# avr_dip.net
KiCad netlist of a schematic drawn in EAGLE
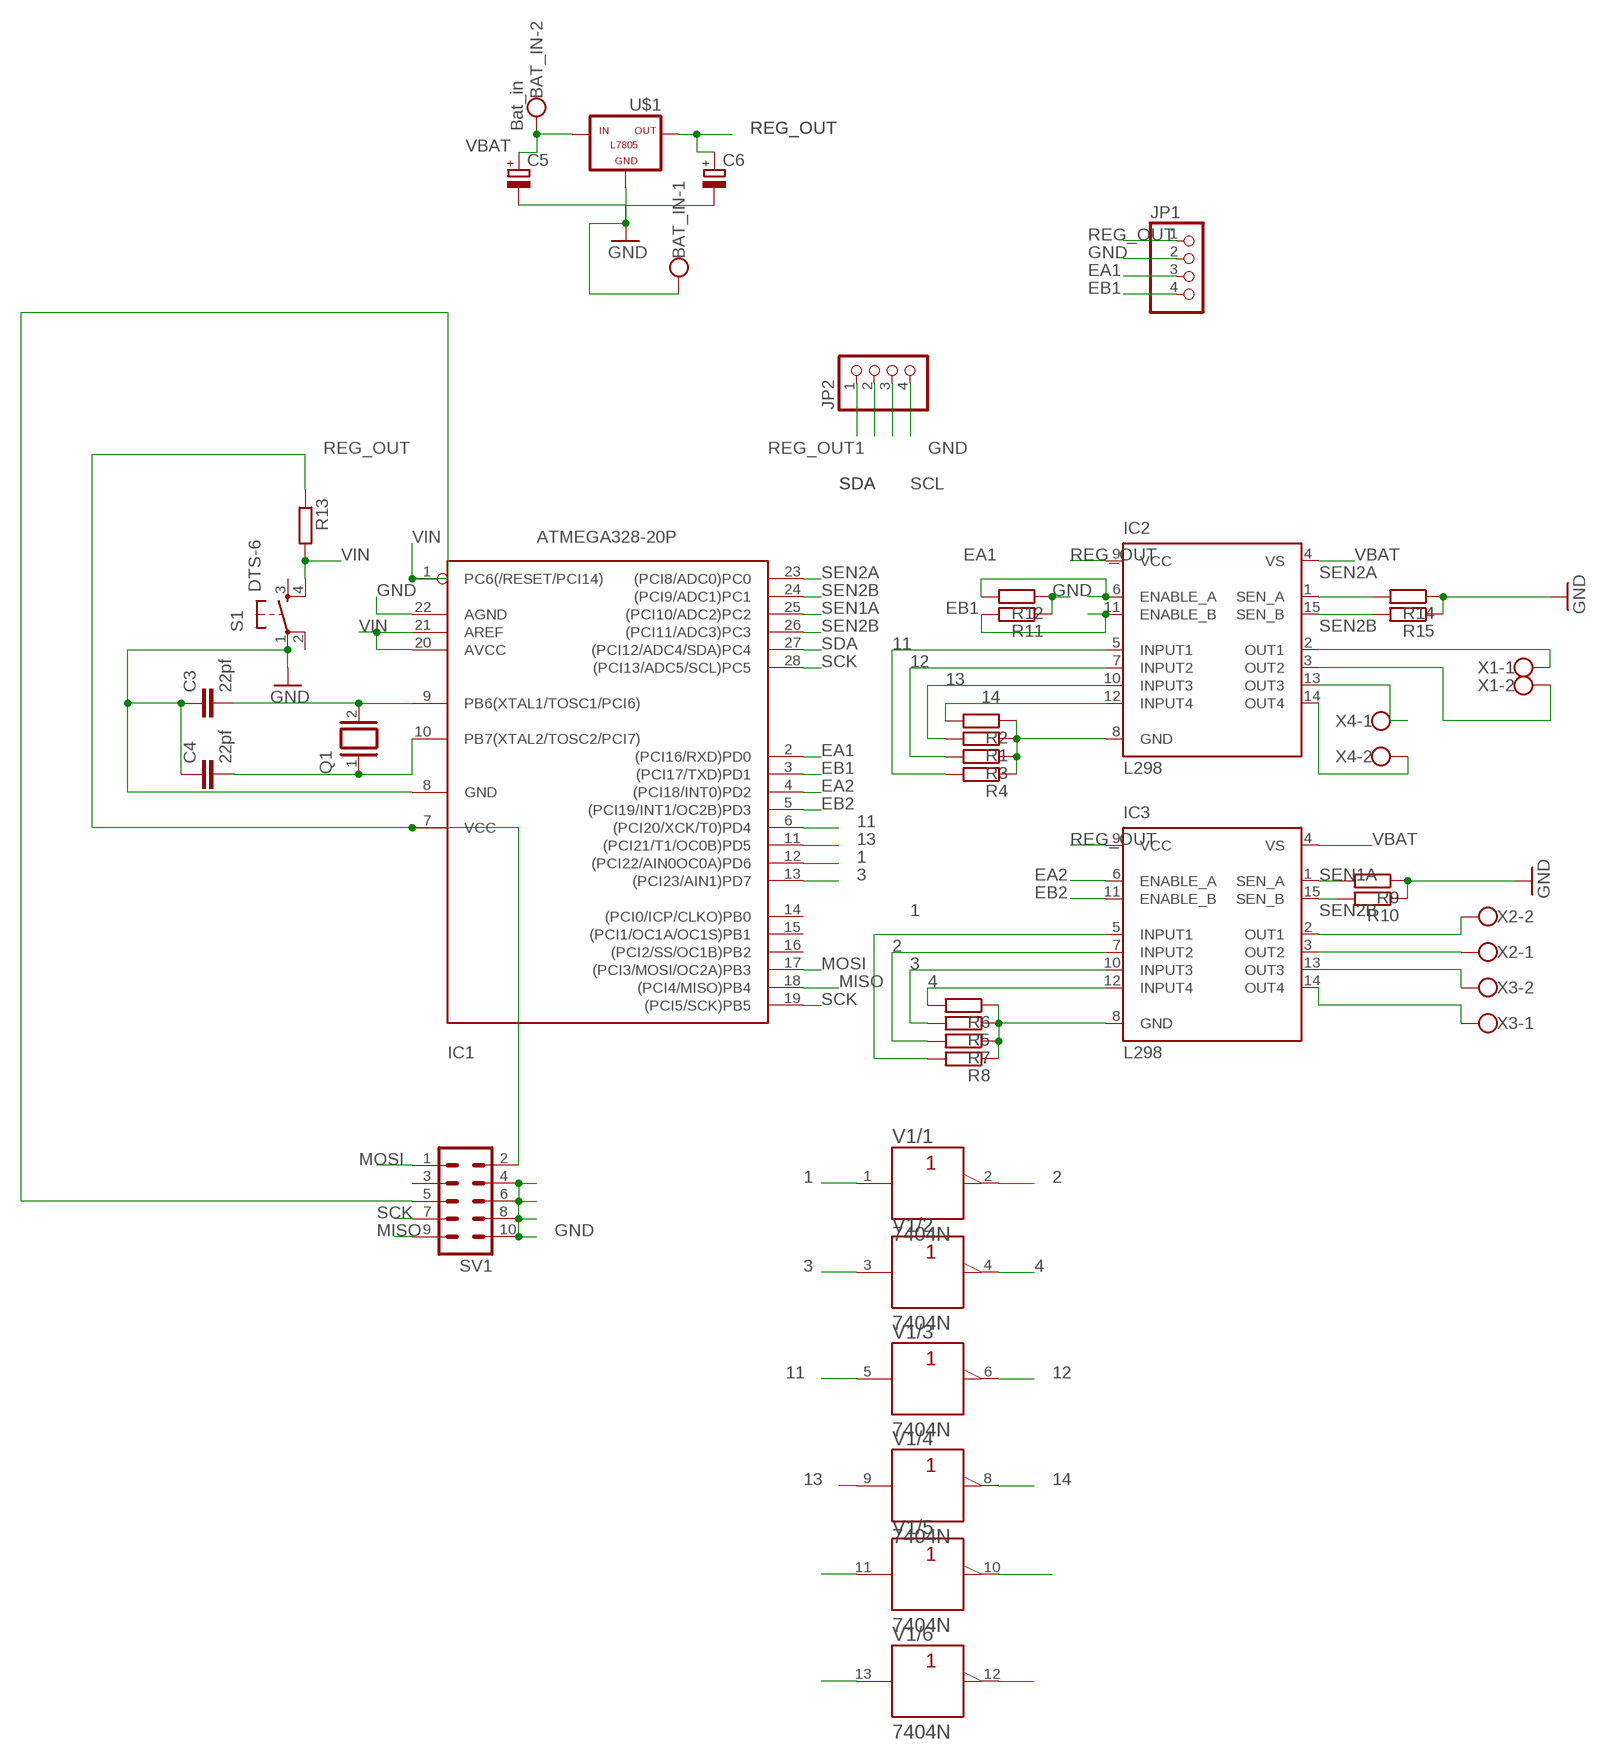
[diagram p0: schematic, sheet 1]

(export (version "E")
  (design (tool "Eeschema 10.0.6"))
  (components
    (comp (ref "BAT_IN")
      (value "Bat_in")
      (footprint "eagle-import:W237-102")
      (fields (field (name "MPN") "237-102"))
      (libsource (lib "eagle-import") (part "W237-102"))
    )
    (comp (ref "C3")
      (value "22pf")
      (footprint "eagle-import:C5B2.5")
      (libsource (lib "eagle-import") (part "C5/2.5"))
    )
    (comp (ref "C4")
      (value "22pf")
      (footprint "eagle-import:C5B2.5")
      (libsource (lib "eagle-import") (part "C5/2.5"))
    )
    (comp (ref "C5")
      (value "CPOL-EUE2-5")
      (footprint "eagle-import:E2-5")
      (libsource (lib "eagle-import") (part "CPOL-EUE2-5"))
    )
    (comp (ref "C6")
      (value "CPOL-EUE2-5")
      (footprint "eagle-import:E2-5")
      (libsource (lib "eagle-import") (part "CPOL-EUE2-5"))
    )
    (comp (ref "IC1")
      (value "ATMEGA328-20P")
      (footprint "eagle-import:DIL28-3")
      (libsource (lib "eagle-import") (part "ATMEGA328P-20"))
    )
    (comp (ref "IC2")
      (value "L298")
      (footprint "eagle-import:MULTIWATT-15")
      (fields (field (name "MPN") "L298N"))
      (libsource (lib "eagle-import") (part "L298"))
    )
    (comp (ref "IC3")
      (value "L298")
      (footprint "eagle-import:MULTIWATT-15")
      (fields (field (name "MPN") "L298N"))
      (libsource (lib "eagle-import") (part "L298"))
    )
    (comp (ref "JP1")
      (value "PINHD-1X4")
      (footprint "eagle-import:1X04")
      (libsource (lib "eagle-import") (part "PINHD-1X4"))
    )
    (comp (ref "JP2")
      (value "PINHD-1X4")
      (footprint "eagle-import:1X04")
      (libsource (lib "eagle-import") (part "PINHD-1X4"))
    )
    (comp (ref "Q1")
      (value "XTAL/S")
      (footprint "eagle-import:QS")
      (libsource (lib "eagle-import") (part "XTAL/S"))
    )
    (comp (ref "R1")
      (value "R-EU_0207/10")
      (footprint "eagle-import:0207_10")
      (libsource (lib "eagle-import") (part "R-EU_0207/10"))
    )
    (comp (ref "R2")
      (value "R-EU_0207/10")
      (footprint "eagle-import:0207_10")
      (libsource (lib "eagle-import") (part "R-EU_0207/10"))
    )
    (comp (ref "R3")
      (value "R-EU_0207/10")
      (footprint "eagle-import:0207_10")
      (libsource (lib "eagle-import") (part "R-EU_0207/10"))
    )
    (comp (ref "R4")
      (value "R-EU_0207/10")
      (footprint "eagle-import:0207_10")
      (libsource (lib "eagle-import") (part "R-EU_0207/10"))
    )
    (comp (ref "R5")
      (value "R-EU_0207/10")
      (footprint "eagle-import:0207_10")
      (libsource (lib "eagle-import") (part "R-EU_0207/10"))
    )
    (comp (ref "R6")
      (value "R-EU_0207/10")
      (footprint "eagle-import:0207_10")
      (libsource (lib "eagle-import") (part "R-EU_0207/10"))
    )
    (comp (ref "R7")
      (value "R-EU_0207/10")
      (footprint "eagle-import:0207_10")
      (libsource (lib "eagle-import") (part "R-EU_0207/10"))
    )
    (comp (ref "R8")
      (value "R-EU_0207/10")
      (footprint "eagle-import:0207_10")
      (libsource (lib "eagle-import") (part "R-EU_0207/10"))
    )
    (comp (ref "R9")
      (value "R-EU_0207/10")
      (footprint "eagle-import:0207_10")
      (libsource (lib "eagle-import") (part "R-EU_0207/10"))
    )
    (comp (ref "R10")
      (value "R-EU_0207/10")
      (footprint "eagle-import:0207_10")
      (libsource (lib "eagle-import") (part "R-EU_0207/10"))
    )
    (comp (ref "R11")
      (value "R-EU_0207/10")
      (footprint "eagle-import:0207_10")
      (libsource (lib "eagle-import") (part "R-EU_0207/10"))
    )
    (comp (ref "R12")
      (value "R-EU_0207/10")
      (footprint "eagle-import:0207_10")
      (libsource (lib "eagle-import") (part "R-EU_0207/10"))
    )
    (comp (ref "R13")
      (value "R-EU_0207/10")
      (footprint "eagle-import:0207_10")
      (libsource (lib "eagle-import") (part "R-EU_0207/10"))
    )
    (comp (ref "R14")
      (value "R-EU_0207/10")
      (footprint "eagle-import:0207_10")
      (libsource (lib "eagle-import") (part "R-EU_0207/10"))
    )
    (comp (ref "R15")
      (value "R-EU_0207/10")
      (footprint "eagle-import:0207_10")
      (libsource (lib "eagle-import") (part "R-EU_0207/10"))
    )
    (comp (ref "S1")
      (value "DTS-6")
      (footprint "eagle-import:DTS-6")
      (libsource (lib "eagle-import") (part "DTS-6"))
    )
    (comp (ref "SV1")
      (value "MA05-2")
      (footprint "eagle-import:MA05-2")
      (libsource (lib "eagle-import") (part "MA05-2"))
    )
    (comp (ref "U$1")
      (value "-L7805")
      (footprint "eagle-import:L7805")
      (libsource (lib "eagle-import") (part "-L7805"))
    )
    (comp (ref "V1")
      (value "7404N")
      (footprint "eagle-import:DIL14")
      (libsource (lib "eagle-import") (part "7404N"))
    )
    (comp (ref "X1")
      (value "W237-102")
      (footprint "eagle-import:W237-102")
      (fields (field (name "MPN") "237-102"))
      (libsource (lib "eagle-import") (part "W237-102"))
    )
    (comp (ref "X2")
      (value "W237-102")
      (footprint "eagle-import:W237-102")
      (fields (field (name "MPN") "237-102"))
      (libsource (lib "eagle-import") (part "W237-102"))
    )
    (comp (ref "X3")
      (value "W237-102")
      (footprint "eagle-import:W237-102")
      (fields (field (name "MPN") "237-102"))
      (libsource (lib "eagle-import") (part "W237-102"))
    )
    (comp (ref "X4")
      (value "W237-102")
      (footprint "eagle-import:W237-102")
      (fields (field (name "MPN") "237-102"))
      (libsource (lib "eagle-import") (part "W237-102"))
    )
  )
  (nets
    (net (code "1") (name "/1") (class "Default")
      (node (ref "IC1") (pin "12") (pinfunction "(PCI22/AIN0OC0A)PD6_12") (pintype "bidirectional"))
      (node (ref "IC3") (pin "5") (pinfunction "INPUT1_5") (pintype "input"))
      (node (ref "R8") (pin "2") (pinfunction "2_2") (pintype "passive"))
      (node (ref "V1") (pin "1") (pinfunction "A_1") (pintype "input"))
    )
    (net (code "2") (name "/2") (class "Default")
      (node (ref "IC3") (pin "7") (pinfunction "INPUT2_7") (pintype "input"))
      (node (ref "R7") (pin "2") (pinfunction "2_2") (pintype "passive"))
      (node (ref "V1") (pin "2") (pinfunction "Y_2") (pintype "output"))
    )
    (net (code "3") (name "/3") (class "Default")
      (node (ref "IC1") (pin "13") (pinfunction "(PCI23/AIN1)PD7_13") (pintype "bidirectional"))
      (node (ref "IC3") (pin "10") (pinfunction "INPUT3_10") (pintype "input"))
      (node (ref "R5") (pin "2") (pinfunction "2_2") (pintype "passive"))
      (node (ref "V1") (pin "3") (pinfunction "A_3") (pintype "input"))
    )
    (net (code "4") (name "/4") (class "Default")
      (node (ref "IC3") (pin "12") (pinfunction "INPUT4_12") (pintype "input"))
      (node (ref "R6") (pin "2") (pinfunction "2_2") (pintype "passive"))
      (node (ref "V1") (pin "4") (pinfunction "Y_4") (pintype "output"))
    )
    (net (code "5") (name "/11") (class "Default")
      (node (ref "IC1") (pin "6") (pinfunction "(PCI20/XCK/T0)PD4_6") (pintype "bidirectional"))
      (node (ref "IC2") (pin "5") (pinfunction "INPUT1_5") (pintype "input"))
      (node (ref "R4") (pin "2") (pinfunction "2_2") (pintype "passive"))
      (node (ref "V1") (pin "5") (pinfunction "A_5") (pintype "input"))
    )
    (net (code "6") (name "/12") (class "Default")
      (node (ref "IC2") (pin "7") (pinfunction "INPUT2_7") (pintype "input"))
      (node (ref "R3") (pin "2") (pinfunction "2_2") (pintype "passive"))
      (node (ref "V1") (pin "6") (pinfunction "Y_6") (pintype "output"))
    )
    (net (code "7") (name "/13") (class "Default")
      (node (ref "IC1") (pin "11") (pinfunction "(PCI21/T1/OC0B)PD5_11") (pintype "bidirectional"))
      (node (ref "IC2") (pin "10") (pinfunction "INPUT3_10") (pintype "input"))
      (node (ref "R1") (pin "2") (pinfunction "2_2") (pintype "passive"))
      (node (ref "V1") (pin "9") (pinfunction "A_9") (pintype "input"))
    )
    (net (code "8") (name "/14") (class "Default")
      (node (ref "IC2") (pin "12") (pinfunction "INPUT4_12") (pintype "input"))
      (node (ref "R2") (pin "2") (pinfunction "2_2") (pintype "passive"))
      (node (ref "V1") (pin "8") (pinfunction "Y_8") (pintype "output"))
    )
    (net (code "9") (name "/EA1") (class "Default")
      (node (ref "IC1") (pin "2") (pinfunction "(PCI16/RXD)PD0_2") (pintype "bidirectional"))
      (node (ref "IC2") (pin "6") (pinfunction "ENABLE_A_6") (pintype "input"))
      (node (ref "JP1") (pin "3") (pinfunction "3_3") (pintype "passive"))
      (node (ref "R12") (pin "2") (pinfunction "2_2") (pintype "passive"))
    )
    (net (code "10") (name "/EA2") (class "Default")
      (node (ref "IC1") (pin "4") (pinfunction "(PCI18/INT0)PD2_4") (pintype "bidirectional"))
      (node (ref "IC3") (pin "6") (pinfunction "ENABLE_A_6") (pintype "input"))
    )
    (net (code "11") (name "/EB1") (class "Default")
      (node (ref "IC1") (pin "3") (pinfunction "(PCI17/TXD)PD1_3") (pintype "bidirectional"))
      (node (ref "IC2") (pin "11") (pinfunction "ENABLE_B_11") (pintype "input"))
      (node (ref "JP1") (pin "4") (pinfunction "4_4") (pintype "passive"))
      (node (ref "R11") (pin "2") (pinfunction "2_2") (pintype "passive"))
    )
    (net (code "12") (name "/EB2") (class "Default")
      (node (ref "IC1") (pin "5") (pinfunction "(PCI19/INT1/OC2B)PD3_5") (pintype "bidirectional"))
      (node (ref "IC3") (pin "11") (pinfunction "ENABLE_B_11") (pintype "input"))
    )
    (net (code "13") (name "/MISO") (class "Default")
      (node (ref "IC1") (pin "18") (pinfunction "(PCI4/MISO)PB4_18") (pintype "bidirectional"))
      (node (ref "SV1") (pin "9") (pinfunction "9_9") (pintype "passive"))
    )
    (net (code "14") (name "/MOSI") (class "Default")
      (node (ref "IC1") (pin "17") (pinfunction "(PCI3/MOSI/OC2A)PB3_17") (pintype "bidirectional"))
      (node (ref "SV1") (pin "1") (pinfunction "1_1") (pintype "passive"))
    )
    (net (code "15") (name "/REG_OUT") (class "Default")
      (node (ref "C6") (pin "+") (pinfunction "+_+") (pintype "passive"))
      (node (ref "IC1") (pin "7") (pinfunction "VCC_7") (pintype "bidirectional"))
      (node (ref "IC2") (pin "9") (pinfunction "VCC_9") (pintype "power_in"))
      (node (ref "IC3") (pin "9") (pinfunction "VCC_9") (pintype "power_in"))
      (node (ref "JP1") (pin "1") (pinfunction "1_1") (pintype "passive"))
      (node (ref "R13") (pin "1") (pinfunction "1_1") (pintype "passive"))
      (node (ref "SV1") (pin "2") (pinfunction "2_2") (pintype "passive"))
      (node (ref "U$1") (pin "OUT") (pinfunction "OUT_OUT") (pintype "passive"))
    )
    (net (code "16") (name "/REG_OUT1") (class "Default")
      (node (ref "JP2") (pin "1") (pinfunction "1_1") (pintype "passive"))
    )
    (net (code "17") (name "/SCK") (class "Default")
      (node (ref "IC1") (pin "19") (pinfunction "(PCI5/SCK)PB5_19") (pintype "bidirectional"))
      (node (ref "IC1") (pin "28") (pinfunction "(PCI13/ADC5/SCL)PC5_28") (pintype "bidirectional"))
      (node (ref "SV1") (pin "7") (pinfunction "7_7") (pintype "passive"))
    )
    (net (code "18") (name "/SCL") (class "Default")
      (node (ref "JP2") (pin "3") (pinfunction "3_3") (pintype "passive"))
    )
    (net (code "19") (name "/SDA") (class "Default")
      (node (ref "IC1") (pin "27") (pinfunction "(PCI12/ADC4/SDA)PC4_27") (pintype "bidirectional"))
      (node (ref "JP2") (pin "2") (pinfunction "2_2") (pintype "passive"))
    )
    (net (code "20") (name "/SEN1A") (class "Default")
      (node (ref "IC1") (pin "25") (pinfunction "(PCI10/ADC2)PC2_25") (pintype "bidirectional"))
      (node (ref "IC3") (pin "1") (pinfunction "SEN_A_1") (pintype "input"))
      (node (ref "R9") (pin "2") (pinfunction "2_2") (pintype "passive"))
    )
    (net (code "21") (name "/SEN2A") (class "Default")
      (node (ref "IC1") (pin "23") (pinfunction "(PCI8/ADC0)PC0_23") (pintype "bidirectional"))
      (node (ref "IC2") (pin "1") (pinfunction "SEN_A_1") (pintype "input"))
      (node (ref "R14") (pin "2") (pinfunction "2_2") (pintype "passive"))
    )
    (net (code "22") (name "/SEN2B") (class "Default")
      (node (ref "IC1") (pin "24") (pinfunction "(PCI9/ADC1)PC1_24") (pintype "bidirectional"))
      (node (ref "IC1") (pin "26") (pinfunction "(PCI11/ADC3)PC3_26") (pintype "bidirectional"))
      (node (ref "IC2") (pin "15") (pinfunction "SEN_B_15") (pintype "input"))
      (node (ref "IC3") (pin "15") (pinfunction "SEN_B_15") (pintype "input"))
      (node (ref "R10") (pin "2") (pinfunction "2_2") (pintype "passive"))
      (node (ref "R15") (pin "2") (pinfunction "2_2") (pintype "passive"))
    )
    (net (code "23") (name "/VBAT") (class "Default")
      (node (ref "BAT_IN") (pin "2") (pinfunction "KL_2") (pintype "passive"))
      (node (ref "C5") (pin "+") (pinfunction "+_+") (pintype "passive"))
      (node (ref "IC2") (pin "4") (pinfunction "VS_4") (pintype "power_in"))
      (node (ref "IC3") (pin "4") (pinfunction "VS_4") (pintype "power_in"))
      (node (ref "U$1") (pin "IN") (pinfunction "IN_IN") (pintype "input"))
    )
    (net (code "24") (name "/VIN") (class "Default")
      (node (ref "IC1") (pin "1") (pinfunction "PC6(/RESET/PCI14)_1") (pintype "bidirectional"))
      (node (ref "IC1") (pin "20") (pinfunction "AVCC_20") (pintype "bidirectional"))
      (node (ref "IC1") (pin "21") (pinfunction "AREF_21") (pintype "bidirectional"))
      (node (ref "R13") (pin "2") (pinfunction "2_2") (pintype "passive"))
      (node (ref "S1") (pin "4") (pinfunction "4_4") (pintype "passive"))
      (node (ref "SV1") (pin "5") (pinfunction "5_5") (pintype "passive"))
    )
    (net (code "25") (name "GND") (class "Default")
      (node (ref "BAT_IN") (pin "1") (pinfunction "KL_1") (pintype "passive"))
      (node (ref "C3") (pin "1") (pinfunction "1_1") (pintype "passive"))
      (node (ref "C4") (pin "1") (pinfunction "1_1") (pintype "passive"))
      (node (ref "C5") (pin "-") (pinfunction "-_-") (pintype "passive"))
      (node (ref "C6") (pin "-") (pinfunction "-_-") (pintype "passive"))
      (node (ref "IC1") (pin "22") (pinfunction "AGND_22") (pintype "bidirectional"))
      (node (ref "IC1") (pin "8") (pinfunction "GND_8") (pintype "bidirectional"))
      (node (ref "JP1") (pin "2") (pinfunction "2_2") (pintype "passive"))
      (node (ref "JP2") (pin "4") (pinfunction "4_4") (pintype "passive"))
      (node (ref "R10") (pin "1") (pinfunction "1_1") (pintype "passive"))
      (node (ref "R11") (pin "1") (pinfunction "1_1") (pintype "passive"))
      (node (ref "R12") (pin "1") (pinfunction "1_1") (pintype "passive"))
      (node (ref "R14") (pin "1") (pinfunction "1_1") (pintype "passive"))
      (node (ref "R15") (pin "1") (pinfunction "1_1") (pintype "passive"))
      (node (ref "R9") (pin "1") (pinfunction "1_1") (pintype "passive"))
      (node (ref "S1") (pin "1") (pinfunction "1_1") (pintype "passive"))
      (node (ref "SV1") (pin "10") (pinfunction "10_10") (pintype "passive"))
      (node (ref "SV1") (pin "4") (pinfunction "4_4") (pintype "passive"))
      (node (ref "SV1") (pin "6") (pinfunction "6_6") (pintype "passive"))
      (node (ref "SV1") (pin "8") (pinfunction "8_8") (pintype "passive"))
      (node (ref "U$1") (pin "GND") (pinfunction "GND_GND") (pintype "input"))
    )
    (net (code "26") (name "Net-(IC1-PB6(XTAL1{slash}TOSC1{slash}PCI6))") (class "Default")
      (node (ref "C3") (pin "2") (pinfunction "2_2") (pintype "passive"))
      (node (ref "IC1") (pin "9") (pinfunction "PB6(XTAL1/TOSC1/PCI6)_9") (pintype "bidirectional"))
      (node (ref "Q1") (pin "2") (pinfunction "2_2") (pintype "passive"))
    )
    (net (code "27") (name "Net-(IC1-PB7(XTAL2{slash}TOSC2{slash}PCI7))") (class "Default")
      (node (ref "C4") (pin "2") (pinfunction "2_2") (pintype "passive"))
      (node (ref "IC1") (pin "10") (pinfunction "PB7(XTAL2/TOSC2/PCI7)_10") (pintype "bidirectional"))
      (node (ref "Q1") (pin "1") (pinfunction "1_1") (pintype "passive"))
    )
    (net (code "28") (name "Net-(IC2-GND)") (class "Default")
      (node (ref "IC2") (pin "8") (pinfunction "GND_8") (pintype "power_in"))
      (node (ref "R1") (pin "1") (pinfunction "1_1") (pintype "passive"))
      (node (ref "R2") (pin "1") (pinfunction "1_1") (pintype "passive"))
      (node (ref "R3") (pin "1") (pinfunction "1_1") (pintype "passive"))
      (node (ref "R4") (pin "1") (pinfunction "1_1") (pintype "passive"))
    )
    (net (code "29") (name "Net-(IC2-OUT1)") (class "Default")
      (node (ref "IC2") (pin "2") (pinfunction "OUT1_2") (pintype "output"))
      (node (ref "X1") (pin "1") (pinfunction "KL_1") (pintype "passive"))
    )
    (net (code "30") (name "Net-(IC2-OUT2)") (class "Default")
      (node (ref "IC2") (pin "3") (pinfunction "OUT2_3") (pintype "output"))
      (node (ref "X1") (pin "2") (pinfunction "KL_2") (pintype "passive"))
    )
    (net (code "31") (name "Net-(IC2-OUT3)") (class "Default")
      (node (ref "IC2") (pin "13") (pinfunction "OUT3_13") (pintype "output"))
      (node (ref "X4") (pin "1") (pinfunction "KL_1") (pintype "passive"))
    )
    (net (code "32") (name "Net-(IC2-OUT4)") (class "Default")
      (node (ref "IC2") (pin "14") (pinfunction "OUT4_14") (pintype "output"))
      (node (ref "X4") (pin "2") (pinfunction "KL_2") (pintype "passive"))
    )
    (net (code "33") (name "Net-(IC3-GND)") (class "Default")
      (node (ref "IC3") (pin "8") (pinfunction "GND_8") (pintype "power_in"))
      (node (ref "R5") (pin "1") (pinfunction "1_1") (pintype "passive"))
      (node (ref "R6") (pin "1") (pinfunction "1_1") (pintype "passive"))
      (node (ref "R7") (pin "1") (pinfunction "1_1") (pintype "passive"))
      (node (ref "R8") (pin "1") (pinfunction "1_1") (pintype "passive"))
    )
    (net (code "34") (name "Net-(IC3-OUT1)") (class "Default")
      (node (ref "IC3") (pin "2") (pinfunction "OUT1_2") (pintype "output"))
      (node (ref "X2") (pin "2") (pinfunction "KL_2") (pintype "passive"))
    )
    (net (code "35") (name "Net-(IC3-OUT2)") (class "Default")
      (node (ref "IC3") (pin "3") (pinfunction "OUT2_3") (pintype "output"))
      (node (ref "X2") (pin "1") (pinfunction "KL_1") (pintype "passive"))
    )
    (net (code "36") (name "Net-(IC3-OUT3)") (class "Default")
      (node (ref "IC3") (pin "13") (pinfunction "OUT3_13") (pintype "output"))
      (node (ref "X3") (pin "2") (pinfunction "KL_2") (pintype "passive"))
    )
    (net (code "37") (name "Net-(IC3-OUT4)") (class "Default")
      (node (ref "IC3") (pin "14") (pinfunction "OUT4_14") (pintype "output"))
      (node (ref "X3") (pin "1") (pinfunction "KL_1") (pintype "passive"))
    )
    (net (code "38") (name "unconnected-(IC1-(PCI0{slash}ICP{slash}CLKO)PB0-Pad14)") (class "Default")
      (node (ref "IC1") (pin "14") (pinfunction "(PCI0/ICP/CLKO)PB0_14") (pintype "bidirectional"))
    )
    (net (code "39") (name "unconnected-(IC1-(PCI1{slash}OC1A{slash}OC1S)PB1-Pad15)") (class "Default")
      (node (ref "IC1") (pin "15") (pinfunction "(PCI1/OC1A/OC1S)PB1_15") (pintype "bidirectional"))
    )
    (net (code "40") (name "unconnected-(IC1-(PCI2{slash}SS{slash}OC1B)PB2-Pad16)") (class "Default")
      (node (ref "IC1") (pin "16") (pinfunction "(PCI2/SS/OC1B)PB2_16") (pintype "bidirectional"))
    )
    (net (code "41") (name "unconnected-(S1-Pad2)") (class "Default")
      (node (ref "S1") (pin "2") (pinfunction "2_2") (pintype "passive"))
    )
    (net (code "42") (name "unconnected-(S1-Pad3)") (class "Default")
      (node (ref "S1") (pin "3") (pinfunction "3_3") (pintype "passive"))
    )
    (net (code "43") (name "unconnected-(SV1-Pad3)") (class "Default")
      (node (ref "SV1") (pin "3") (pinfunction "3_3") (pintype "passive"))
    )
    (net (code "44") (name "unconnected-(V1G-A-Pad11)") (class "Default")
      (node (ref "V1") (pin "11") (pinfunction "A_11") (pintype "input"))
    )
    (net (code "45") (name "unconnected-(V1G-Y-Pad10)") (class "Default")
      (node (ref "V1") (pin "10") (pinfunction "Y_10") (pintype "output"))
    )
    (net (code "46") (name "unconnected-(V1H-A-Pad13)") (class "Default")
      (node (ref "V1") (pin "13") (pinfunction "A_13") (pintype "input"))
    )
    (net (code "47") (name "unconnected-(V1H-Y-Pad12)") (class "Default")
      (node (ref "V1") (pin "12") (pinfunction "Y_12") (pintype "output"))
    )
  )
)
